# DAC_Schematic.net
KiCad netlist of a schematic drawn in Altium Designer
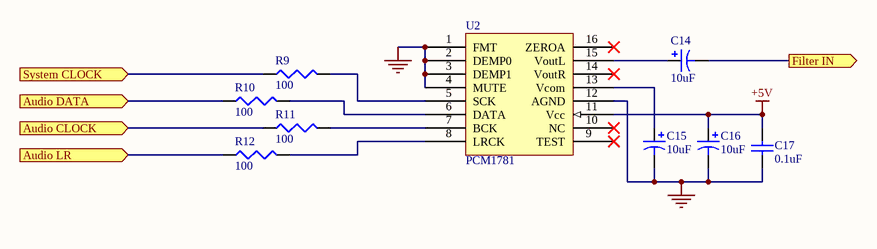
[diagram p0: DAC.Schematic.SchDoc]

(export (version "E")
  (design (tool "Eeschema 10.0.6"))
  (components
    (comp (ref "C14")
      (value "10uF")
      (footprint "CAPC1608N")
      (description "Polarized Capacitor (Radial)")
      (fields (field (name "PUBLISHER") "Altium Limited"))
      (libsource (lib "Miscellaneous Devices") (part "Cap Pol1"))
    )
    (comp (ref "C15")
      (value "10uF")
      (footprint "CAPC1608N")
      (description "Polarized Capacitor (Radial)")
      (fields (field (name "PUBLISHER") "Altium Limited"))
      (libsource (lib "Miscellaneous Devices") (part "Cap Pol1"))
    )
    (comp (ref "C16")
      (value "10uF")
      (footprint "CAPC1608N")
      (description "Polarized Capacitor (Radial)")
      (fields (field (name "PUBLISHER") "Altium Limited"))
      (libsource (lib "Miscellaneous Devices") (part "Cap Pol1"))
    )
    (comp (ref "C17")
      (value "0.1uF")
      (footprint "CAPC1608N")
      (description "Capacitor (Semiconductor SIM Model)")
      (fields (field (name "PUBLISHER") "Altium Limited"))
      (libsource (lib "Miscellaneous Devices") (part "Cap Semi"))
    )
    (comp (ref "R9")
      (value "100")
      (footprint "CAPC1608N")
      (description "Resistor")
      (fields (field (name "PUBLISHER") "Altium Limited"))
      (libsource (lib "Miscellaneous Devices") (part "Res3"))
    )
    (comp (ref "R10")
      (value "100")
      (footprint "CAPC1608N")
      (description "Resistor")
      (fields (field (name "PUBLISHER") "Altium Limited"))
      (libsource (lib "Miscellaneous Devices") (part "Res3"))
    )
    (comp (ref "R11")
      (value "100")
      (footprint "CAPC1608N")
      (description "Resistor")
      (fields (field (name "PUBLISHER") "Altium Limited"))
      (libsource (lib "Miscellaneous Devices") (part "Res3"))
    )
    (comp (ref "R12")
      (value "100")
      (footprint "CAPC1608N")
      (description "Resistor")
      (fields (field (name "PUBLISHER") "Altium Limited"))
      (libsource (lib "Miscellaneous Devices") (part "Res3"))
    )
    (comp (ref "U2")
      (value "PCM1781")
      (footprint "PCM1781")
      (libsource (lib "SynthyTwo.Components") (part "PCM1781 DAC"))
    )
  )
  (nets
    (net (code "1") (name "+5V") (class "Default")
      (node (ref "C16") (pin "1") (pinfunction "1_1") (pintype "passive"))
      (node (ref "C17") (pin "2") (pinfunction "2_2") (pintype "passive"))
      (node (ref "U2") (pin "11") (pinfunction "Vcc_11") (pintype "input"))
    )
    (net (code "2") (name "/Audio CLOCK") (class "Default")
      (node (ref "R11") (pin "1") (pinfunction "1_1") (pintype "passive"))
    )
    (net (code "3") (name "/Audio DATA") (class "Default")
      (node (ref "R10") (pin "1") (pinfunction "1_1") (pintype "passive"))
    )
    (net (code "4") (name "/Audio LR") (class "Default")
      (node (ref "R12") (pin "1") (pinfunction "1_1") (pintype "passive"))
    )
    (net (code "5") (name "/Filter IN") (class "Default")
      (node (ref "C14") (pin "2") (pinfunction "2_2") (pintype "passive"))
    )
    (net (code "6") (name "/System CLOCK") (class "Default")
      (node (ref "R9") (pin "1") (pinfunction "1_1") (pintype "passive"))
    )
    (net (code "7") (name "<NO NET>") (class "Default")
      (node (ref "C15") (pin "2") (pinfunction "2_2") (pintype "passive"))
      (node (ref "C16") (pin "2") (pinfunction "2_2") (pintype "passive"))
      (node (ref "C17") (pin "1") (pinfunction "1_1") (pintype "passive"))
      (node (ref "U2") (pin "1") (pinfunction "FMT_1") (pintype "passive"))
      (node (ref "U2") (pin "12") (pinfunction "AGND_12") (pintype "passive"))
      (node (ref "U2") (pin "2") (pinfunction "DEMP0_2") (pintype "passive"))
      (node (ref "U2") (pin "3") (pinfunction "DEMP1_3") (pintype "passive"))
      (node (ref "U2") (pin "4") (pinfunction "MUTE_4") (pintype "passive"))
    )
    (net (code "8") (name "Net-(U2-BCK)") (class "Default")
      (node (ref "R11") (pin "2") (pinfunction "2_2") (pintype "passive"))
      (node (ref "U2") (pin "7") (pinfunction "BCK_7") (pintype "passive"))
    )
    (net (code "9") (name "Net-(U2-DATA)") (class "Default")
      (node (ref "R10") (pin "2") (pinfunction "2_2") (pintype "passive"))
      (node (ref "U2") (pin "6") (pinfunction "DATA_6") (pintype "passive"))
    )
    (net (code "10") (name "Net-(U2-LRCK)") (class "Default")
      (node (ref "R12") (pin "2") (pinfunction "2_2") (pintype "passive"))
      (node (ref "U2") (pin "8") (pinfunction "LRCK_8") (pintype "passive"))
    )
    (net (code "11") (name "Net-(U2-SCK)") (class "Default")
      (node (ref "R9") (pin "2") (pinfunction "2_2") (pintype "passive"))
      (node (ref "U2") (pin "5") (pinfunction "SCK_5") (pintype "passive"))
    )
    (net (code "12") (name "Net-(U2-Vcom)") (class "Default")
      (node (ref "C15") (pin "1") (pinfunction "1_1") (pintype "passive"))
      (node (ref "U2") (pin "13") (pinfunction "Vcom_13") (pintype "passive"))
    )
    (net (code "13") (name "Net-(U2-VoutL)") (class "Default")
      (node (ref "C14") (pin "1") (pinfunction "1_1") (pintype "passive"))
      (node (ref "U2") (pin "15") (pinfunction "VoutL_15") (pintype "passive"))
    )
    (net (code "14") (name "unconnected-(U2-NC-Pad10)") (class "Default")
      (node (ref "U2") (pin "10") (pinfunction "NC_10") (pintype "passive+no_connect"))
    )
    (net (code "15") (name "unconnected-(U2-TEST-Pad9)") (class "Default")
      (node (ref "U2") (pin "9") (pinfunction "TEST_9") (pintype "passive+no_connect"))
    )
    (net (code "16") (name "unconnected-(U2-VoutR-Pad14)") (class "Default")
      (node (ref "U2") (pin "14") (pinfunction "VoutR_14") (pintype "passive+no_connect"))
    )
    (net (code "17") (name "unconnected-(U2-ZEROA-Pad16)") (class "Default")
      (node (ref "U2") (pin "16") (pinfunction "ZEROA_16") (pintype "passive+no_connect"))
    )
  )
)
